# Microprocessor_Module_328.net
KiCad netlist of a schematic drawn in Altium Designer
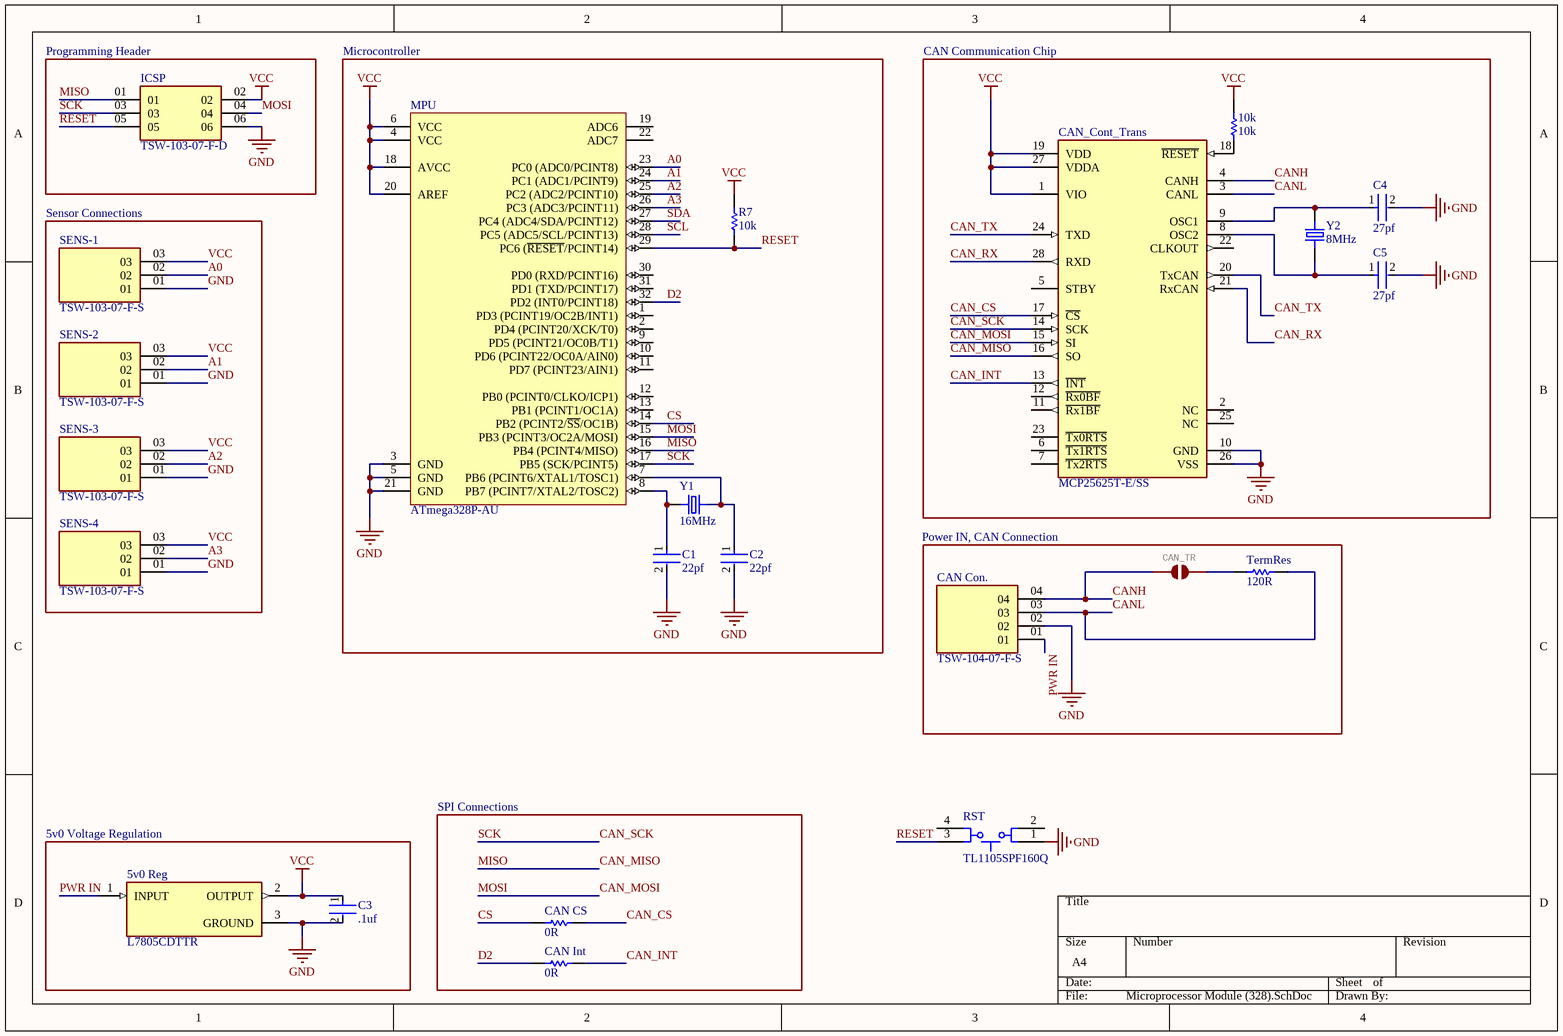
[diagram p0: Microprocessor Module (328).SchDoc]

(export (version "E")
  (design (tool "Eeschema 10.0.6"))
  (components
    (comp (ref "5v0 Reg")
      (value "L7805CDTTR")
      (footprint "VREG_L7805CDTTR")
      (fields (field (name "MF") "STMicroelectronics"))
      (libsource (lib "L7805CDTTR") (part "L7805CDTTR"))
    )
    (comp (ref "10k")
      (value "10k")
      (footprint "RESC2013X60X40LL20T25")
      (fields (field (name "PART NUMBER") "ERA6AEB473V") (field (name "MANUFACTURER") "Panasonic"))
      (libsource (lib "Altium Content Vault") (part "RES"))
    )
    (comp (ref "C1")
      (value "22pf")
      (footprint "FP-GRM21B-0_15-IPC_C")
      (description "Chip Multilayer Ceramic Capacitors for General Purpose, 0805, 10uF, X5R, 15%, 10%, 25V")
      (fields (field (name "VOLTAGE") "25V") (field (name "TOLERANCE") "10%"))
      (libsource (lib "Altium Content Vault") (part "b4654b650e69147ec39a6b967a45e02"))
    )
    (comp (ref "C2")
      (value "22pf")
      (footprint "FP-GRM21B-0_15-IPC_C")
      (description "Chip Multilayer Ceramic Capacitors for General Purpose, 0805, 10uF, X5R, 15%, 10%, 25V")
      (fields (field (name "VOLTAGE") "25V") (field (name "TOLERANCE") "10%"))
      (libsource (lib "Altium Content Vault") (part "b4654b650e69147ec39a6b967a45e02"))
    )
    (comp (ref "C3")
      (value ".1uf")
      (footprint "FP-GRM21B-0_15-IPC_C")
      (description "Chip Multilayer Ceramic Capacitors for General Purpose, 0805, 10uF, X5R, 15%, 10%, 25V")
      (fields (field (name "VOLTAGE") "25V") (field (name "TOLERANCE") "10%"))
      (libsource (lib "Altium Content Vault") (part "b4654b650e69147ec39a6b967a45e02"))
    )
    (comp (ref "C4")
      (value "27pf")
      (footprint "FP-GRM21B-0_15-IPC_C")
      (description "Chip Multilayer Ceramic Capacitors for General Purpose, 0805, 10uF, X5R, 15%, 10%, 25V")
      (fields (field (name "VOLTAGE") "25V") (field (name "TOLERANCE") "10%"))
      (libsource (lib "Altium Content Vault") (part "b4654b650e69147ec39a6b967a45e02"))
    )
    (comp (ref "C5")
      (value "27pf")
      (footprint "FP-GRM21B-0_15-IPC_C")
      (description "Chip Multilayer Ceramic Capacitors for General Purpose, 0805, 10uF, X5R, 15%, 10%, 25V")
      (fields (field (name "VOLTAGE") "25V") (field (name "TOLERANCE") "10%"))
      (libsource (lib "Altium Content Vault") (part "b4654b650e69147ec39a6b967a45e02"))
    )
    (comp (ref "CAN Con.")
      (value "TSW-104-07-F-S")
      (footprint "SAMTEC_TSW-104-07-F-S")
      (fields (field (name "MF") "Samtec"))
      (libsource (lib "TSW-104-07-F-S") (part "TSW-104-07-F-S"))
    )
    (comp (ref "CAN CS")
      (value "0R")
      (footprint "RESC2013X60X40LL20T25")
      (fields (field (name "PART NUMBER") "ERA6AEB473V") (field (name "MANUFACTURER") "Panasonic"))
      (libsource (lib "Altium Content Vault") (part "RES"))
    )
    (comp (ref "CAN Int")
      (value "0R")
      (footprint "RESC2013X60X40LL20T25")
      (fields (field (name "PART NUMBER") "ERA6AEB473V") (field (name "MANUFACTURER") "Panasonic"))
      (libsource (lib "Altium Content Vault") (part "RES"))
    )
    (comp (ref "CAN_Cont_Trans")
      (value "MCP25625T-E/SS")
      (footprint "FP-C04-073-IPC_B")
      (description "IC TRANSCEIVER 1/1 28SSOP")
      (libsource (lib "Altium Content Vault") (part "1eb43db0d86e80dbea2ef2edec005e1"))
    )
    (comp (ref "CAN_TR")
      (value "~")
      (footprint "SMT-JUMPER_2_NO_SILK")
      (libsource (lib "SparkFun-Jumpers.Library") (part "JUMPER-SMT_2_NO_SILK"))
    )
    (comp (ref "ICSP")
      (value "TSW-103-07-F-D")
      (footprint "SAMTEC_TSW-103-07-F-D")
      (fields (field (name "MF") "Samtec"))
      (libsource (lib "TSW-103-07-F-D") (part "TSW-103-07-F-D"))
    )
    (comp (ref "MPU")
      (value "ATmega328P-AU")
      (footprint "32A_M")
      (libsource (lib "Altium Content Vault") (part "MC-8B-ATM48-SQ32"))
    )
    (comp (ref "R7")
      (value "10k")
      (footprint "RESC2013X60X40LL20T25")
      (fields (field (name "PART NUMBER") "ERA6AEB473V") (field (name "MANUFACTURER") "Panasonic"))
      (libsource (lib "Altium Content Vault") (part "RES"))
    )
    (comp (ref "RST")
      (value "TL1105SPF160Q")
      (footprint "ESWI-TL1105SPF_V")
      (description "Tact Switch, SPST-NO, 50 mA, 12 VDC, -20 to 70 degC, 4-Pin THD, RoHS, Bulk")
      (fields (field (name "MANUFACTURER") "E-Switch"))
      (libsource (lib "Altium Content Vault") (part "SW-SPST-NO-4"))
    )
    (comp (ref "SENS-1")
      (value "TSW-103-07-F-S")
      (footprint "SAMTEC_TSW-103-07-F-S")
      (fields (field (name "MF") "Samtec"))
      (libsource (lib "TSW-103-07-F-S") (part "TSW-103-07-F-S"))
    )
    (comp (ref "SENS-2")
      (value "TSW-103-07-F-S")
      (footprint "SAMTEC_TSW-103-07-F-S")
      (fields (field (name "MF") "Samtec"))
      (libsource (lib "TSW-103-07-F-S") (part "TSW-103-07-F-S"))
    )
    (comp (ref "SENS-3")
      (value "TSW-103-07-F-S")
      (footprint "SAMTEC_TSW-103-07-F-S")
      (fields (field (name "MF") "Samtec"))
      (libsource (lib "TSW-103-07-F-S") (part "TSW-103-07-F-S"))
    )
    (comp (ref "SENS-4")
      (value "TSW-103-07-F-S")
      (footprint "SAMTEC_TSW-103-07-F-S")
      (fields (field (name "MF") "Samtec"))
      (libsource (lib "TSW-103-07-F-S") (part "TSW-103-07-F-S"))
    )
    (comp (ref "TermRes")
      (value "120R")
      (footprint "RESC2013X60X40LL20T25")
      (fields (field (name "PART NUMBER") "ERA6AEB473V") (field (name "MANUFACTURER") "Panasonic"))
      (libsource (lib "Altium Content Vault") (part "RES"))
    )
    (comp (ref "Y1")
      (value "16MHz")
      (footprint "XTAL_ECS-080-20-5PX-TR")
      (description "8 MHz Â±30ppm Crystal 20pF 60 Ohms HC-49/US")
      (fields (field (name "MP") "ECS-080-20-5PX-TR") (field (name "MF") "ECS"))
      (libsource (lib "ECS-080-20-5PX-TR") (part "ECS-080-20-5PX-TR"))
    )
    (comp (ref "Y2")
      (value "8MHz")
      (footprint "XTAL_ECS-080-20-5PX-TR")
      (description "8 MHz Â±30ppm Crystal 20pF 60 Ohms HC-49/US")
      (fields (field (name "MP") "ECS-080-20-5PX-TR") (field (name "MF") "ECS"))
      (libsource (lib "ECS-080-20-5PX-TR") (part "ECS-080-20-5PX-TR"))
    )
  )
  (nets
    (net (code "1") (name "/A0") (class "Default")
      (node (ref "MPU") (pin "23") (pinfunction "PC0_(ADC0/PCINT8)_23") (pintype "bidirectional"))
      (node (ref "SENS-1") (pin "02") (pinfunction "02_02") (pintype "passive"))
    )
    (net (code "2") (name "/A1") (class "Default")
      (node (ref "MPU") (pin "24") (pinfunction "PC1_(ADC1/PCINT9)_24") (pintype "bidirectional"))
      (node (ref "SENS-2") (pin "02") (pinfunction "02_02") (pintype "passive"))
    )
    (net (code "3") (name "/A2") (class "Default")
      (node (ref "MPU") (pin "25") (pinfunction "PC2_(ADC2/PCINT10)_25") (pintype "bidirectional"))
      (node (ref "SENS-3") (pin "02") (pinfunction "02_02") (pintype "passive"))
    )
    (net (code "4") (name "/A3") (class "Default")
      (node (ref "MPU") (pin "26") (pinfunction "PC3_(ADC3/PCINT11)_26") (pintype "bidirectional"))
      (node (ref "SENS-4") (pin "02") (pinfunction "02_02") (pintype "passive"))
    )
    (net (code "5") (name "/CANH") (class "Default")
      (node (ref "CAN Con.") (pin "04") (pinfunction "04_04") (pintype "passive"))
      (node (ref "CAN_Cont_Trans") (pin "4") (pinfunction "CANH_4") (pintype "passive"))
      (node (ref "CAN_TR") (pin "1") (pinfunction "1_1") (pintype "passive"))
    )
    (net (code "6") (name "/CANL") (class "Default")
      (node (ref "CAN Con.") (pin "03") (pinfunction "03_03") (pintype "passive"))
      (node (ref "CAN_Cont_Trans") (pin "3") (pinfunction "CANL_3") (pintype "passive"))
      (node (ref "TermRes") (pin "1") (pinfunction "1_1") (pintype "passive"))
    )
    (net (code "7") (name "/CAN_CS") (class "Default")
      (node (ref "CAN CS") (pin "2") (pinfunction "2_2") (pintype "passive"))
      (node (ref "CAN_Cont_Trans") (pin "17") (pinfunction "~{CS}_17") (pintype "input"))
    )
    (net (code "8") (name "/CAN_INT") (class "Default")
      (node (ref "CAN Int") (pin "2") (pinfunction "2_2") (pintype "passive"))
      (node (ref "CAN_Cont_Trans") (pin "13") (pinfunction "~{INT}_13") (pintype "output"))
    )
    (net (code "9") (name "/CAN_MISO") (class "Default")
      (node (ref "CAN_Cont_Trans") (pin "16") (pinfunction "SO_16") (pintype "output"))
      (node (ref "ICSP") (pin "01") (pinfunction "01_01") (pintype "passive"))
      (node (ref "MPU") (pin "16") (pinfunction "PB4_(PCINT4/MISO)_16") (pintype "bidirectional"))
    )
    (net (code "10") (name "/CAN_MOSI") (class "Default")
      (node (ref "CAN_Cont_Trans") (pin "15") (pinfunction "SI_15") (pintype "input"))
      (node (ref "ICSP") (pin "04") (pinfunction "04_04") (pintype "passive"))
      (node (ref "MPU") (pin "15") (pinfunction "PB3_(PCINT3/OC2A/MOSI)_15") (pintype "bidirectional"))
    )
    (net (code "11") (name "/CAN_RX") (class "Default")
      (node (ref "CAN_Cont_Trans") (pin "21") (pinfunction "RxCAN_21") (pintype "input"))
      (node (ref "CAN_Cont_Trans") (pin "28") (pinfunction "RXD_28") (pintype "output"))
    )
    (net (code "12") (name "/CAN_SCK") (class "Default")
      (node (ref "CAN_Cont_Trans") (pin "14") (pinfunction "SCK_14") (pintype "input"))
      (node (ref "ICSP") (pin "03") (pinfunction "03_03") (pintype "passive"))
      (node (ref "MPU") (pin "17") (pinfunction "PB5_(SCK/PCINT5)_17") (pintype "bidirectional"))
    )
    (net (code "13") (name "/CAN_TX") (class "Default")
      (node (ref "CAN_Cont_Trans") (pin "20") (pinfunction "TxCAN_20") (pintype "output"))
      (node (ref "CAN_Cont_Trans") (pin "24") (pinfunction "TXD_24") (pintype "input"))
    )
    (net (code "14") (name "/CS") (class "Default")
      (node (ref "CAN CS") (pin "1") (pinfunction "1_1") (pintype "passive"))
      (node (ref "MPU") (pin "14") (pinfunction "PB2_(PCINT2/~{SS}/OC1B)_14") (pintype "bidirectional"))
    )
    (net (code "15") (name "/D2") (class "Default")
      (node (ref "CAN Int") (pin "1") (pinfunction "1_1") (pintype "passive"))
      (node (ref "MPU") (pin "32") (pinfunction "PD2_(INT0/PCINT18)_32") (pintype "bidirectional"))
    )
    (net (code "16") (name "/PWR IN") (class "Default")
      (node (ref "5v0 Reg") (pin "1") (pinfunction "INPUT_1") (pintype "input"))
      (node (ref "CAN Con.") (pin "01") (pinfunction "01_01") (pintype "passive"))
    )
    (net (code "17") (name "/RESET") (class "Default")
      (node (ref "ICSP") (pin "05") (pinfunction "05_05") (pintype "passive"))
      (node (ref "MPU") (pin "29") (pinfunction "PC6_(~{RESET}/PCINT14)_29") (pintype "bidirectional"))
      (node (ref "R7") (pin "1") (pinfunction "1_1") (pintype "passive"))
      (node (ref "RST") (pin "3") (pinfunction "3_3") (pintype "passive"))
    )
    (net (code "18") (name "/SCL") (class "Default")
      (node (ref "MPU") (pin "28") (pinfunction "PC5_(ADC5/SCL/PCINT13)_28") (pintype "bidirectional"))
    )
    (net (code "19") (name "/SDA") (class "Default")
      (node (ref "MPU") (pin "27") (pinfunction "PC4_(ADC4/SDA/PCINT12)_27") (pintype "bidirectional"))
    )
    (net (code "20") (name "GND") (class "Default")
      (node (ref "5v0 Reg") (pin "3") (pinfunction "GROUND_3") (pintype "power_in"))
      (node (ref "C1") (pin "2") (pinfunction "2_2") (pintype "passive"))
      (node (ref "C2") (pin "2") (pinfunction "2_2") (pintype "passive"))
      (node (ref "C3") (pin "2") (pinfunction "2_2") (pintype "passive"))
      (node (ref "C4") (pin "2") (pinfunction "2_2") (pintype "passive"))
      (node (ref "C5") (pin "2") (pinfunction "2_2") (pintype "passive"))
      (node (ref "CAN Con.") (pin "02") (pinfunction "02_02") (pintype "passive"))
      (node (ref "CAN_Cont_Trans") (pin "10") (pinfunction "GND_10") (pintype "power_in"))
      (node (ref "CAN_Cont_Trans") (pin "26") (pinfunction "VSS_26") (pintype "power_in"))
      (node (ref "ICSP") (pin "06") (pinfunction "06_06") (pintype "passive"))
      (node (ref "MPU") (pin "21") (pinfunction "GND_21") (pintype "power_in"))
      (node (ref "MPU") (pin "3") (pinfunction "GND_3") (pintype "power_in"))
      (node (ref "MPU") (pin "5") (pinfunction "GND_5") (pintype "power_in"))
      (node (ref "RST") (pin "1") (pinfunction "1_1") (pintype "passive"))
      (node (ref "SENS-1") (pin "01") (pinfunction "01_01") (pintype "passive"))
      (node (ref "SENS-2") (pin "01") (pinfunction "01_01") (pintype "passive"))
      (node (ref "SENS-3") (pin "01") (pinfunction "01_01") (pintype "passive"))
      (node (ref "SENS-4") (pin "01") (pinfunction "01_01") (pintype "passive"))
    )
    (net (code "21") (name "Net-(CAN_Cont_Trans-OSC1)") (class "Default")
      (node (ref "C4") (pin "1") (pinfunction "1_1") (pintype "passive"))
      (node (ref "CAN_Cont_Trans") (pin "9") (pinfunction "OSC1_9") (pintype "passive"))
      (node (ref "Y2") (pin "2") (pinfunction "2_2") (pintype "passive"))
    )
    (net (code "22") (name "Net-(CAN_Cont_Trans-OSC2)") (class "Default")
      (node (ref "C5") (pin "1") (pinfunction "1_1") (pintype "passive"))
      (node (ref "CAN_Cont_Trans") (pin "8") (pinfunction "OSC2_8") (pintype "passive"))
      (node (ref "Y2") (pin "1") (pinfunction "1_1") (pintype "passive"))
    )
    (net (code "23") (name "Net-(CAN_Cont_Trans-~{RESET})") (class "Default")
      (node (ref "10k") (pin "1") (pinfunction "1_1") (pintype "passive"))
      (node (ref "CAN_Cont_Trans") (pin "18") (pinfunction "~{RESET}_18") (pintype "input"))
    )
    (net (code "24") (name "Net-(CAN_TR-Pad2)") (class "Default")
      (node (ref "CAN_TR") (pin "2") (pinfunction "2_2") (pintype "passive"))
      (node (ref "TermRes") (pin "2") (pinfunction "2_2") (pintype "passive"))
    )
    (net (code "25") (name "Net-(MPU-PB6_(PCINT6{slash}XTAL1{slash}TOSC1))") (class "Default")
      (node (ref "C2") (pin "1") (pinfunction "1_1") (pintype "passive"))
      (node (ref "MPU") (pin "7") (pinfunction "PB6_(PCINT6/XTAL1/TOSC1)_7") (pintype "bidirectional"))
      (node (ref "Y1") (pin "1") (pinfunction "1_1") (pintype "passive"))
    )
    (net (code "26") (name "Net-(MPU-PB7_(PCINT7{slash}XTAL2{slash}TOSC2))") (class "Default")
      (node (ref "C1") (pin "1") (pinfunction "1_1") (pintype "passive"))
      (node (ref "MPU") (pin "8") (pinfunction "PB7_(PCINT7/XTAL2/TOSC2)_8") (pintype "bidirectional"))
      (node (ref "Y1") (pin "2") (pinfunction "2_2") (pintype "passive"))
    )
    (net (code "27") (name "VCC") (class "Default")
      (node (ref "10k") (pin "2") (pinfunction "2_2") (pintype "passive"))
      (node (ref "5v0 Reg") (pin "2") (pinfunction "OUTPUT_2") (pintype "output"))
      (node (ref "C3") (pin "1") (pinfunction "1_1") (pintype "passive"))
      (node (ref "CAN_Cont_Trans") (pin "1") (pinfunction "VIO_1") (pintype "power_in"))
      (node (ref "CAN_Cont_Trans") (pin "19") (pinfunction "VDD_19") (pintype "power_in"))
      (node (ref "CAN_Cont_Trans") (pin "27") (pinfunction "VDDA_27") (pintype "power_in"))
      (node (ref "ICSP") (pin "02") (pinfunction "02_02") (pintype "passive"))
      (node (ref "MPU") (pin "18") (pinfunction "AVCC_18") (pintype "power_in"))
      (node (ref "MPU") (pin "20") (pinfunction "AREF_20") (pintype "passive"))
      (node (ref "MPU") (pin "4") (pinfunction "VCC_4") (pintype "power_in"))
      (node (ref "MPU") (pin "6") (pinfunction "VCC_6") (pintype "power_in"))
      (node (ref "R7") (pin "2") (pinfunction "2_2") (pintype "passive"))
      (node (ref "SENS-1") (pin "03") (pinfunction "03_03") (pintype "passive"))
      (node (ref "SENS-2") (pin "03") (pinfunction "03_03") (pintype "passive"))
      (node (ref "SENS-3") (pin "03") (pinfunction "03_03") (pintype "passive"))
      (node (ref "SENS-4") (pin "03") (pinfunction "03_03") (pintype "passive"))
    )
    (net (code "28") (name "unconnected-(CAN_Cont_Trans-CLKOUT-Pad22)") (class "Default")
      (node (ref "CAN_Cont_Trans") (pin "22") (pinfunction "CLKOUT_22") (pintype "output"))
    )
    (net (code "29") (name "unconnected-(CAN_Cont_Trans-NC-Pad2)") (class "Default")
      (node (ref "CAN_Cont_Trans") (pin "2") (pinfunction "NC_2") (pintype "passive"))
    )
    (net (code "30") (name "unconnected-(CAN_Cont_Trans-NC-Pad25)") (class "Default")
      (node (ref "CAN_Cont_Trans") (pin "25") (pinfunction "NC_25") (pintype "passive"))
    )
    (net (code "31") (name "unconnected-(CAN_Cont_Trans-STBY-Pad5)") (class "Default")
      (node (ref "CAN_Cont_Trans") (pin "5") (pinfunction "STBY_5") (pintype "passive"))
    )
    (net (code "32") (name "unconnected-(CAN_Cont_Trans-~{Rx0BF}-Pad12)") (class "Default")
      (node (ref "CAN_Cont_Trans") (pin "12") (pinfunction "~{Rx0BF}_12") (pintype "output"))
    )
    (net (code "33") (name "unconnected-(CAN_Cont_Trans-~{Rx1BF}-Pad11)") (class "Default")
      (node (ref "CAN_Cont_Trans") (pin "11") (pinfunction "~{Rx1BF}_11") (pintype "output"))
    )
    (net (code "34") (name "unconnected-(CAN_Cont_Trans-~{Tx0RTS}-Pad23)") (class "Default")
      (node (ref "CAN_Cont_Trans") (pin "23") (pinfunction "~{Tx0RTS}_23") (pintype "passive"))
    )
    (net (code "35") (name "unconnected-(CAN_Cont_Trans-~{Tx1RTS}-Pad6)") (class "Default")
      (node (ref "CAN_Cont_Trans") (pin "6") (pinfunction "~{Tx1RTS}_6") (pintype "passive"))
    )
    (net (code "36") (name "unconnected-(CAN_Cont_Trans-~{Tx2RTS}-Pad7)") (class "Default")
      (node (ref "CAN_Cont_Trans") (pin "7") (pinfunction "~{Tx2RTS}_7") (pintype "passive"))
    )
    (net (code "37") (name "unconnected-(MPU-ADC6-Pad19)") (class "Default")
      (node (ref "MPU") (pin "19") (pinfunction "ADC6_19") (pintype "passive"))
    )
    (net (code "38") (name "unconnected-(MPU-ADC7-Pad22)") (class "Default")
      (node (ref "MPU") (pin "22") (pinfunction "ADC7_22") (pintype "passive"))
    )
    (net (code "39") (name "unconnected-(MPU-PB0_(PCINT0{slash}CLKO{slash}ICP1)-Pad12)") (class "Default")
      (node (ref "MPU") (pin "12") (pinfunction "PB0_(PCINT0/CLKO/ICP1)_12") (pintype "bidirectional"))
    )
    (net (code "40") (name "unconnected-(MPU-PB1_(PCINT1{slash}OC1A)-Pad13)") (class "Default")
      (node (ref "MPU") (pin "13") (pinfunction "PB1_(PCINT1/OC1A)_13") (pintype "bidirectional"))
    )
    (net (code "41") (name "unconnected-(MPU-PD0_(RXD{slash}PCINT16)-Pad30)") (class "Default")
      (node (ref "MPU") (pin "30") (pinfunction "PD0_(RXD/PCINT16)_30") (pintype "bidirectional"))
    )
    (net (code "42") (name "unconnected-(MPU-PD1_(TXD{slash}PCINT17)-Pad31)") (class "Default")
      (node (ref "MPU") (pin "31") (pinfunction "PD1_(TXD/PCINT17)_31") (pintype "bidirectional"))
    )
    (net (code "43") (name "unconnected-(MPU-PD3_(PCINT19{slash}OC2B{slash}INT1)-Pad1)") (class "Default")
      (node (ref "MPU") (pin "1") (pinfunction "PD3_(PCINT19/OC2B/INT1)_1") (pintype "bidirectional"))
    )
    (net (code "44") (name "unconnected-(MPU-PD4_(PCINT20{slash}XCK{slash}T0)-Pad2)") (class "Default")
      (node (ref "MPU") (pin "2") (pinfunction "PD4_(PCINT20/XCK/T0)_2") (pintype "bidirectional"))
    )
    (net (code "45") (name "unconnected-(MPU-PD5_(PCINT21{slash}OC0B{slash}T1)-Pad9)") (class "Default")
      (node (ref "MPU") (pin "9") (pinfunction "PD5_(PCINT21/OC0B/T1)_9") (pintype "bidirectional"))
    )
    (net (code "46") (name "unconnected-(MPU-PD6_(PCINT22{slash}OC0A{slash}AIN0)-Pad10)") (class "Default")
      (node (ref "MPU") (pin "10") (pinfunction "PD6_(PCINT22/OC0A/AIN0)_10") (pintype "bidirectional"))
    )
    (net (code "47") (name "unconnected-(MPU-PD7_(PCINT23{slash}AIN1)-Pad11)") (class "Default")
      (node (ref "MPU") (pin "11") (pinfunction "PD7_(PCINT23/AIN1)_11") (pintype "bidirectional"))
    )
    (net (code "48") (name "unconnected-(RST-Pad2)") (class "Default")
      (node (ref "RST") (pin "2") (pinfunction "2_2") (pintype "passive"))
    )
    (net (code "49") (name "unconnected-(RST-Pad4)") (class "Default")
      (node (ref "RST") (pin "4") (pinfunction "4_4") (pintype "passive"))
    )
  )
)
